# EDU_A3_PCB_1_v1.net
KiCad netlist of a schematic drawn in EasyEDA Pro
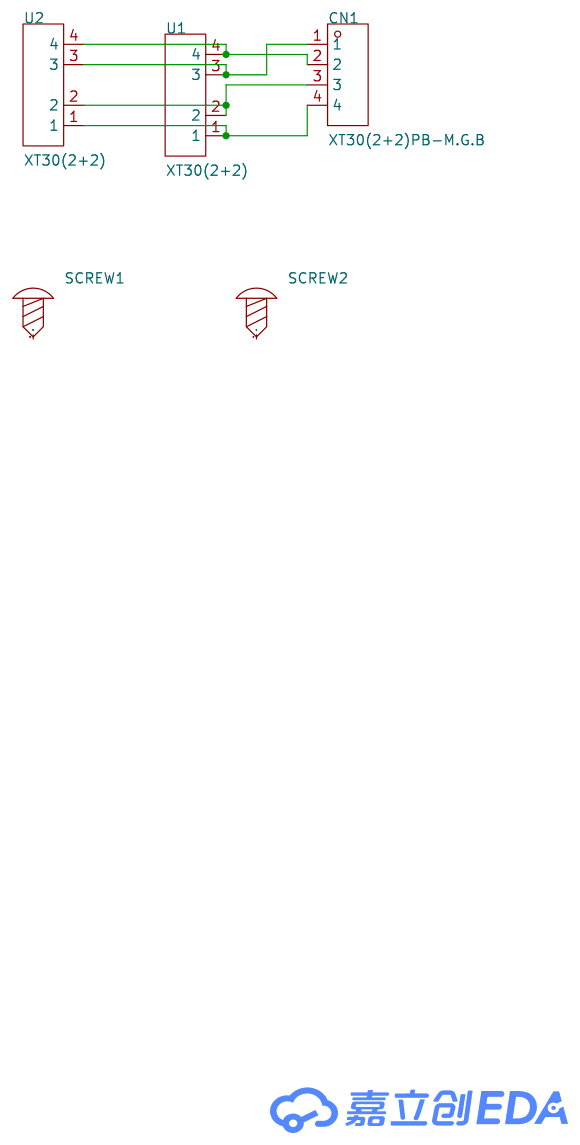
[diagram p0: schematic sheet]

(export (version "E")
  (design (tool "Eeschema 10.0.6"))
  (components
    (comp (ref "CN1")
      (value "XT30(2+2)PB-M.G.B")
      (footprint "easyedapro:CONN-TH_XT30PB-M")
      (fields (field (name "Manufacturer") "AMASS(艾迈斯)"))
      (libsource (lib "easyedapro") (part "XT30(2+2)PB-M.G.B"))
    )
    (comp (ref "SCREW1")
      (value "~")
      (footprint "easyedapro:M3螺丝")
      (libsource (lib "easyedapro") (part "螺丝孔"))
    )
    (comp (ref "SCREW2")
      (value "~")
      (footprint "easyedapro:M3螺丝")
      (libsource (lib "easyedapro") (part "螺丝孔"))
    )
    (comp (ref "U1")
      (value "XT30(2+2)")
      (footprint "easyedapro:CONN-TH_XT30-2-2")
      (libsource (lib "easyedapro") (part "XT30(2+2)"))
    )
    (comp (ref "U2")
      (value "XT30(2+2)")
      (footprint "easyedapro:CONN-TH_XT30-2-2")
      (libsource (lib "easyedapro") (part "XT30(2+2)"))
    )
  )
  (nets
    (net (code "1") (name "Net-(CN1-Pad1)") (class "Default")
      (node (ref "CN1") (pin "1") (pinfunction "1_1") (pintype "unspecified"))
      (node (ref "U1") (pin "3") (pinfunction "3_3") (pintype "unspecified"))
      (node (ref "U2") (pin "3") (pinfunction "3_3") (pintype "unspecified"))
    )
    (net (code "2") (name "Net-(CN1-Pad2)") (class "Default")
      (node (ref "CN1") (pin "2") (pinfunction "2_2") (pintype "unspecified"))
      (node (ref "U1") (pin "4") (pinfunction "4_4") (pintype "unspecified"))
      (node (ref "U2") (pin "4") (pinfunction "4_4") (pintype "unspecified"))
    )
    (net (code "3") (name "Net-(CN1-Pad3)") (class "Default")
      (node (ref "CN1") (pin "3") (pinfunction "3_3") (pintype "unspecified"))
      (node (ref "U1") (pin "2") (pinfunction "2_2") (pintype "unspecified"))
      (node (ref "U2") (pin "2") (pinfunction "2_2") (pintype "unspecified"))
    )
    (net (code "4") (name "Net-(CN1-Pad4)") (class "Default")
      (node (ref "CN1") (pin "4") (pinfunction "4_4") (pintype "unspecified"))
      (node (ref "U1") (pin "1") (pinfunction "1_1") (pintype "unspecified"))
      (node (ref "U2") (pin "1") (pinfunction "1_1") (pintype "unspecified"))
    )
    (net (code "5") (name "unconnected-(SCREW1-Pad1)") (class "Default")
      (node (ref "SCREW1") (pin "1") (pinfunction "1_1") (pintype "input"))
    )
    (net (code "6") (name "unconnected-(SCREW2-Pad1)") (class "Default")
      (node (ref "SCREW2") (pin "1") (pinfunction "1_1") (pintype "input"))
    )
  )
)
